# OneSLiPoCharger.net
KiCad netlist of a schematic drawn in EAGLE
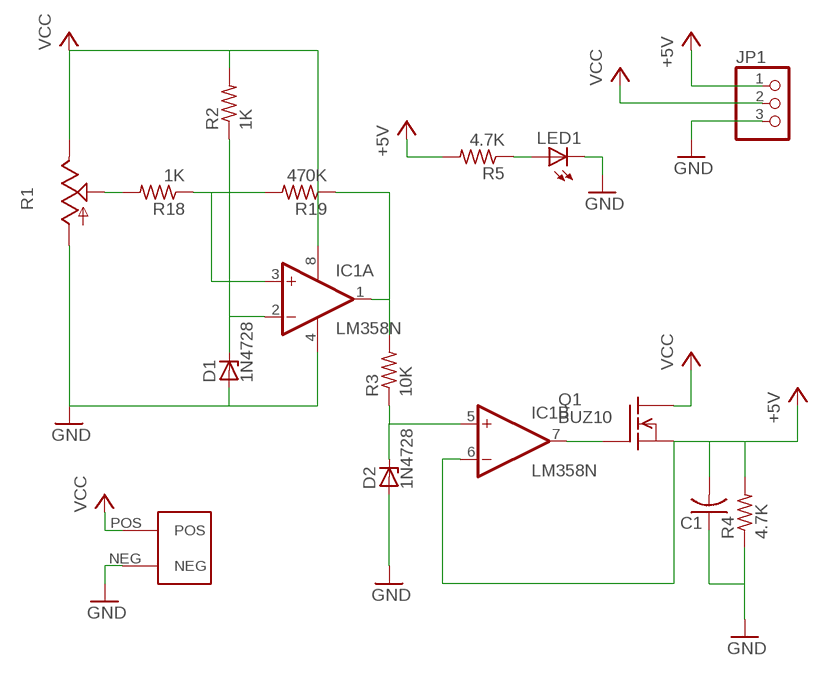
[diagram p0: schematic, sheet 1]
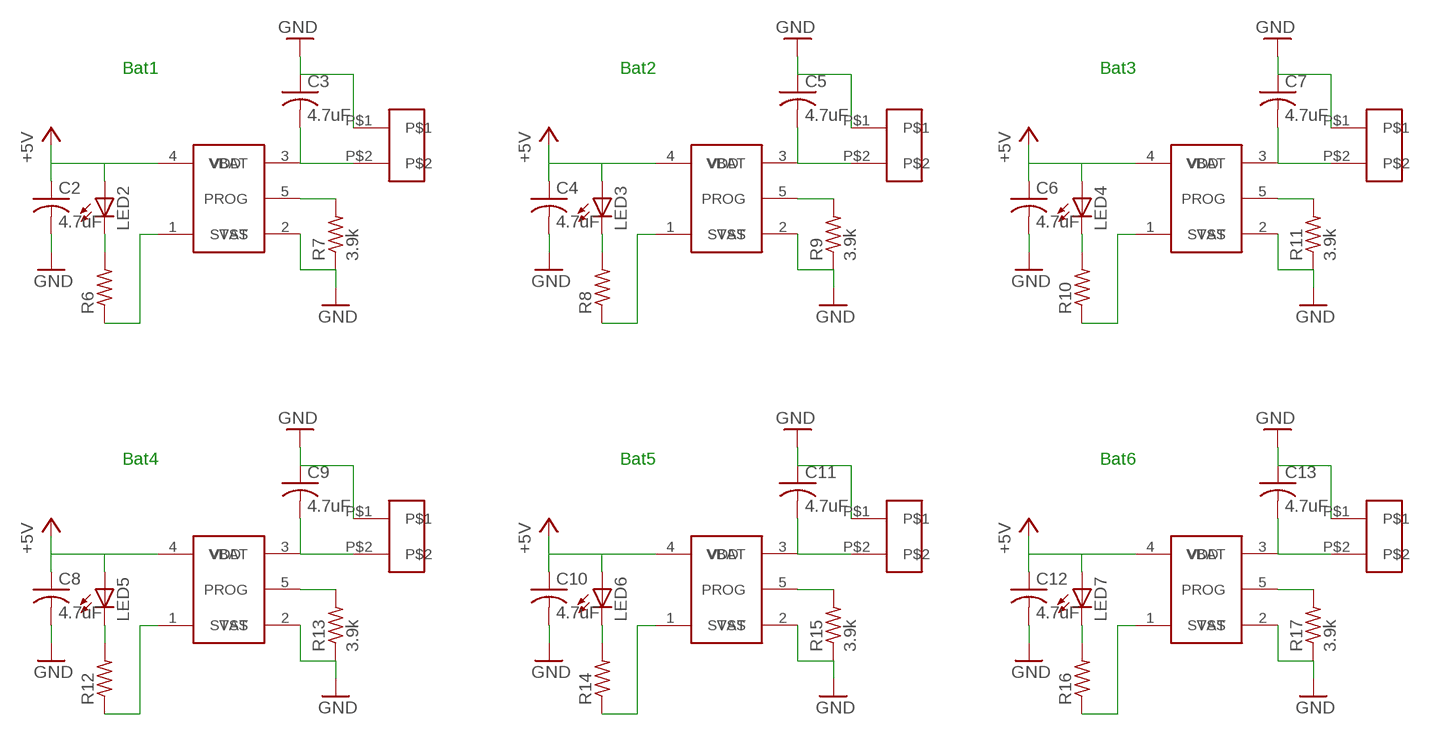
[diagram p1: schematic, sheet 2]

(export (version "E")
  (design (tool "Eeschema 10.0.6"))
  (components
    (comp (ref "C1")
      (value "C-US025-025X050")
      (footprint "eagle-import:C025-025X050")
      (libsource (lib "eagle-import") (part "C-US025-025X050"))
    )
    (comp (ref "D1")
      (value "1N4728")
      (footprint "eagle-import:DO41Z10")
      (libsource (lib "eagle-import") (part "1N4728"))
    )
    (comp (ref "D2")
      (value "1N4728")
      (footprint "eagle-import:DO41Z10")
      (libsource (lib "eagle-import") (part "1N4728"))
    )
    (comp (ref "IC1")
      (value "LM358N")
      (footprint "eagle-import:DIL08")
      (libsource (lib "eagle-import") (part "LM358N"))
    )
    (comp (ref "JP1")
      (value "PINHD-1X3")
      (footprint "eagle-import:1X03")
      (libsource (lib "eagle-import") (part "PINHD-1X3"))
    )
    (comp (ref "LED1")
      (value "LED3MM")
      (footprint "eagle-import:LED3MM")
      (libsource (lib "eagle-import") (part "LED3MM"))
    )
    (comp (ref "Q1")
      (value "BUZ10")
      (footprint "eagle-import:TO220")
      (libsource (lib "eagle-import") (part "BUZ10"))
    )
    (comp (ref "R1")
      (value "TRIM_US-B25P")
      (footprint "eagle-import:B25P")
      (libsource (lib "eagle-import") (part "TRIM_US-B25P"))
    )
    (comp (ref "R2")
      (value "1K")
      (footprint "eagle-import:0207_10")
      (libsource (lib "eagle-import") (part "R-US_0207/10"))
    )
    (comp (ref "R3")
      (value "10K")
      (footprint "eagle-import:0207_10")
      (libsource (lib "eagle-import") (part "R-US_0207/10"))
    )
    (comp (ref "R4")
      (value "4.7K")
      (footprint "eagle-import:0207_10")
      (libsource (lib "eagle-import") (part "R-US_0207/10"))
    )
    (comp (ref "R5")
      (value "4.7K")
      (footprint "eagle-import:0207_10")
      (libsource (lib "eagle-import") (part "R-US_0207/10"))
    )
    (comp (ref "R18")
      (value "1K")
      (footprint "eagle-import:0207_10")
      (libsource (lib "eagle-import") (part "R-US_0207/10"))
    )
    (comp (ref "R19")
      (value "470K")
      (footprint "eagle-import:0207_10")
      (libsource (lib "eagle-import") (part "R-US_0207/10"))
    )
    (comp (ref "U$3")
      (value "XT60")
      (footprint "eagle-import:XT60")
      (libsource (lib "eagle-import") (part "XT60"))
    )
    (comp (ref "C2")
      (value "4.7uF")
      (footprint "eagle-import:C0805")
      (libsource (lib "eagle-import") (part "C-USC0805"))
    )
    (comp (ref "C3")
      (value "4.7uF")
      (footprint "eagle-import:C0805")
      (libsource (lib "eagle-import") (part "C-USC0805"))
    )
    (comp (ref "C4")
      (value "4.7uF")
      (footprint "eagle-import:C0805")
      (libsource (lib "eagle-import") (part "C-USC0805"))
    )
    (comp (ref "C5")
      (value "4.7uF")
      (footprint "eagle-import:C0805")
      (libsource (lib "eagle-import") (part "C-USC0805"))
    )
    (comp (ref "C6")
      (value "4.7uF")
      (footprint "eagle-import:C0805")
      (libsource (lib "eagle-import") (part "C-USC0805"))
    )
    (comp (ref "C7")
      (value "4.7uF")
      (footprint "eagle-import:C0805")
      (libsource (lib "eagle-import") (part "C-USC0805"))
    )
    (comp (ref "C8")
      (value "4.7uF")
      (footprint "eagle-import:C0805")
      (libsource (lib "eagle-import") (part "C-USC0805"))
    )
    (comp (ref "C9")
      (value "4.7uF")
      (footprint "eagle-import:C0805")
      (libsource (lib "eagle-import") (part "C-USC0805"))
    )
    (comp (ref "C10")
      (value "4.7uF")
      (footprint "eagle-import:C0805")
      (libsource (lib "eagle-import") (part "C-USC0805"))
    )
    (comp (ref "C11")
      (value "4.7uF")
      (footprint "eagle-import:C0805")
      (libsource (lib "eagle-import") (part "C-USC0805"))
    )
    (comp (ref "C12")
      (value "4.7uF")
      (footprint "eagle-import:C0805")
      (libsource (lib "eagle-import") (part "C-USC0805"))
    )
    (comp (ref "C13")
      (value "4.7uF")
      (footprint "eagle-import:C0805")
      (libsource (lib "eagle-import") (part "C-USC0805"))
    )
    (comp (ref "LED2")
      (value "LED3MM")
      (footprint "eagle-import:LED3MM")
      (libsource (lib "eagle-import") (part "LED3MM"))
    )
    (comp (ref "LED3")
      (value "LED3MM")
      (footprint "eagle-import:LED3MM")
      (libsource (lib "eagle-import") (part "LED3MM"))
    )
    (comp (ref "LED4")
      (value "LED3MM")
      (footprint "eagle-import:LED3MM")
      (libsource (lib "eagle-import") (part "LED3MM"))
    )
    (comp (ref "LED5")
      (value "LED3MM")
      (footprint "eagle-import:LED3MM")
      (libsource (lib "eagle-import") (part "LED3MM"))
    )
    (comp (ref "LED6")
      (value "LED3MM")
      (footprint "eagle-import:LED3MM")
      (libsource (lib "eagle-import") (part "LED3MM"))
    )
    (comp (ref "LED7")
      (value "LED3MM")
      (footprint "eagle-import:LED3MM")
      (libsource (lib "eagle-import") (part "LED3MM"))
    )
    (comp (ref "R6")
      (value "R-US_M0805")
      (footprint "eagle-import:M0805")
      (libsource (lib "eagle-import") (part "R-US_M0805"))
    )
    (comp (ref "R7")
      (value "3.9k")
      (footprint "eagle-import:M0805")
      (libsource (lib "eagle-import") (part "R-US_M0805"))
    )
    (comp (ref "R8")
      (value "R-US_M0805")
      (footprint "eagle-import:M0805")
      (libsource (lib "eagle-import") (part "R-US_M0805"))
    )
    (comp (ref "R9")
      (value "3.9k")
      (footprint "eagle-import:M0805")
      (libsource (lib "eagle-import") (part "R-US_M0805"))
    )
    (comp (ref "R10")
      (value "R-US_M0805")
      (footprint "eagle-import:M0805")
      (libsource (lib "eagle-import") (part "R-US_M0805"))
    )
    (comp (ref "R11")
      (value "3.9k")
      (footprint "eagle-import:M0805")
      (libsource (lib "eagle-import") (part "R-US_M0805"))
    )
    (comp (ref "R12")
      (value "R-US_M0805")
      (footprint "eagle-import:M0805")
      (libsource (lib "eagle-import") (part "R-US_M0805"))
    )
    (comp (ref "R13")
      (value "3.9k")
      (footprint "eagle-import:M0805")
      (libsource (lib "eagle-import") (part "R-US_M0805"))
    )
    (comp (ref "R14")
      (value "R-US_M0805")
      (footprint "eagle-import:M0805")
      (libsource (lib "eagle-import") (part "R-US_M0805"))
    )
    (comp (ref "R15")
      (value "3.9k")
      (footprint "eagle-import:M0805")
      (libsource (lib "eagle-import") (part "R-US_M0805"))
    )
    (comp (ref "R16")
      (value "R-US_M0805")
      (footprint "eagle-import:M0805")
      (libsource (lib "eagle-import") (part "R-US_M0805"))
    )
    (comp (ref "R17")
      (value "3.9k")
      (footprint "eagle-import:M0805")
      (libsource (lib "eagle-import") (part "R-US_M0805"))
    )
    (comp (ref "U$1")
      (value "MCP73831")
      (footprint "eagle-import:MCP73831-SOT23")
      (libsource (lib "eagle-import") (part "MCP73831"))
    )
    (comp (ref "U$2")
      (value "PICOBLADE-2PIN")
      (footprint "eagle-import:PICOBLADE-2PIN")
      (libsource (lib "eagle-import") (part "PICOBLADE-2PIN"))
    )
    (comp (ref "U$4")
      (value "MCP73831")
      (footprint "eagle-import:MCP73831-SOT23")
      (libsource (lib "eagle-import") (part "MCP73831"))
    )
    (comp (ref "U$5")
      (value "PICOBLADE-2PIN")
      (footprint "eagle-import:PICOBLADE-2PIN")
      (libsource (lib "eagle-import") (part "PICOBLADE-2PIN"))
    )
    (comp (ref "U$6")
      (value "MCP73831")
      (footprint "eagle-import:MCP73831-SOT23")
      (libsource (lib "eagle-import") (part "MCP73831"))
    )
    (comp (ref "U$7")
      (value "PICOBLADE-2PIN")
      (footprint "eagle-import:PICOBLADE-2PIN")
      (libsource (lib "eagle-import") (part "PICOBLADE-2PIN"))
    )
    (comp (ref "U$8")
      (value "MCP73831")
      (footprint "eagle-import:MCP73831-SOT23")
      (libsource (lib "eagle-import") (part "MCP73831"))
    )
    (comp (ref "U$9")
      (value "PICOBLADE-2PIN")
      (footprint "eagle-import:PICOBLADE-2PIN")
      (libsource (lib "eagle-import") (part "PICOBLADE-2PIN"))
    )
    (comp (ref "U$10")
      (value "MCP73831")
      (footprint "eagle-import:MCP73831-SOT23")
      (libsource (lib "eagle-import") (part "MCP73831"))
    )
    (comp (ref "U$11")
      (value "PICOBLADE-2PIN")
      (footprint "eagle-import:PICOBLADE-2PIN")
      (libsource (lib "eagle-import") (part "PICOBLADE-2PIN"))
    )
    (comp (ref "U$12")
      (value "MCP73831")
      (footprint "eagle-import:MCP73831-SOT23")
      (libsource (lib "eagle-import") (part "MCP73831"))
    )
    (comp (ref "U$13")
      (value "PICOBLADE-2PIN")
      (footprint "eagle-import:PICOBLADE-2PIN")
      (libsource (lib "eagle-import") (part "PICOBLADE-2PIN"))
    )
  )
  (nets
    (net (code "1") (name "+5V") (class "Default")
      (node (ref "C1") (pin "2") (pinfunction "2_2") (pintype "passive"))
      (node (ref "C10") (pin "1") (pinfunction "1_1") (pintype "passive"))
      (node (ref "C12") (pin "1") (pinfunction "1_1") (pintype "passive"))
      (node (ref "C2") (pin "1") (pinfunction "1_1") (pintype "passive"))
      (node (ref "C4") (pin "1") (pinfunction "1_1") (pintype "passive"))
      (node (ref "C6") (pin "1") (pinfunction "1_1") (pintype "passive"))
      (node (ref "C8") (pin "1") (pinfunction "1_1") (pintype "passive"))
      (node (ref "IC1") (pin "6") (pinfunction "-IN_6") (pintype "input"))
      (node (ref "JP1") (pin "1") (pinfunction "1_1") (pintype "passive"))
      (node (ref "LED2") (pin "A") (pinfunction "A_A") (pintype "passive"))
      (node (ref "LED3") (pin "A") (pinfunction "A_A") (pintype "passive"))
      (node (ref "LED4") (pin "A") (pinfunction "A_A") (pintype "passive"))
      (node (ref "LED5") (pin "A") (pinfunction "A_A") (pintype "passive"))
      (node (ref "LED6") (pin "A") (pinfunction "A_A") (pintype "passive"))
      (node (ref "LED7") (pin "A") (pinfunction "A_A") (pintype "passive"))
      (node (ref "Q1") (pin "3") (pinfunction "S_3") (pintype "passive"))
      (node (ref "R4") (pin "2") (pinfunction "2_2") (pintype "passive"))
      (node (ref "R5") (pin "2") (pinfunction "2_2") (pintype "passive"))
      (node (ref "U$1") (pin "4") (pinfunction "VDD_4") (pintype "bidirectional"))
      (node (ref "U$10") (pin "4") (pinfunction "VDD_4") (pintype "bidirectional"))
      (node (ref "U$12") (pin "4") (pinfunction "VDD_4") (pintype "bidirectional"))
      (node (ref "U$4") (pin "4") (pinfunction "VDD_4") (pintype "bidirectional"))
      (node (ref "U$6") (pin "4") (pinfunction "VDD_4") (pintype "bidirectional"))
      (node (ref "U$8") (pin "4") (pinfunction "VDD_4") (pintype "bidirectional"))
    )
    (net (code "2") (name "GND") (class "Default")
      (node (ref "C1") (pin "1") (pinfunction "1_1") (pintype "passive"))
      (node (ref "C10") (pin "2") (pinfunction "2_2") (pintype "passive"))
      (node (ref "C11") (pin "1") (pinfunction "1_1") (pintype "passive"))
      (node (ref "C12") (pin "2") (pinfunction "2_2") (pintype "passive"))
      (node (ref "C13") (pin "1") (pinfunction "1_1") (pintype "passive"))
      (node (ref "C2") (pin "2") (pinfunction "2_2") (pintype "passive"))
      (node (ref "C3") (pin "1") (pinfunction "1_1") (pintype "passive"))
      (node (ref "C4") (pin "2") (pinfunction "2_2") (pintype "passive"))
      (node (ref "C5") (pin "1") (pinfunction "1_1") (pintype "passive"))
      (node (ref "C6") (pin "2") (pinfunction "2_2") (pintype "passive"))
      (node (ref "C7") (pin "1") (pinfunction "1_1") (pintype "passive"))
      (node (ref "C8") (pin "2") (pinfunction "2_2") (pintype "passive"))
      (node (ref "C9") (pin "1") (pinfunction "1_1") (pintype "passive"))
      (node (ref "D1") (pin "A") (pinfunction "A_A") (pintype "passive"))
      (node (ref "D2") (pin "A") (pinfunction "A_A") (pintype "passive"))
      (node (ref "IC1") (pin "4") (pinfunction "V-_4") (pintype "power_in"))
      (node (ref "JP1") (pin "3") (pinfunction "3_3") (pintype "passive"))
      (node (ref "LED1") (pin "K") (pinfunction "C_K") (pintype "passive"))
      (node (ref "R1") (pin "A") (pinfunction "A_A") (pintype "passive"))
      (node (ref "R11") (pin "1") (pinfunction "1_1") (pintype "passive"))
      (node (ref "R13") (pin "1") (pinfunction "1_1") (pintype "passive"))
      (node (ref "R15") (pin "1") (pinfunction "1_1") (pintype "passive"))
      (node (ref "R17") (pin "1") (pinfunction "1_1") (pintype "passive"))
      (node (ref "R4") (pin "1") (pinfunction "1_1") (pintype "passive"))
      (node (ref "R7") (pin "1") (pinfunction "1_1") (pintype "passive"))
      (node (ref "R9") (pin "1") (pinfunction "1_1") (pintype "passive"))
      (node (ref "U$1") (pin "2") (pinfunction "VSS_2") (pintype "bidirectional"))
      (node (ref "U$10") (pin "2") (pinfunction "VSS_2") (pintype "bidirectional"))
      (node (ref "U$11") (pin "P$1") (pinfunction "P$1_P$1") (pintype "bidirectional"))
      (node (ref "U$12") (pin "2") (pinfunction "VSS_2") (pintype "bidirectional"))
      (node (ref "U$13") (pin "P$1") (pinfunction "P$1_P$1") (pintype "bidirectional"))
      (node (ref "U$2") (pin "P$1") (pinfunction "P$1_P$1") (pintype "bidirectional"))
      (node (ref "U$3") (pin "NEG") (pinfunction "NEG_NEG") (pintype "bidirectional"))
      (node (ref "U$4") (pin "2") (pinfunction "VSS_2") (pintype "bidirectional"))
      (node (ref "U$5") (pin "P$1") (pinfunction "P$1_P$1") (pintype "bidirectional"))
      (node (ref "U$6") (pin "2") (pinfunction "VSS_2") (pintype "bidirectional"))
      (node (ref "U$7") (pin "P$1") (pinfunction "P$1_P$1") (pintype "bidirectional"))
      (node (ref "U$8") (pin "2") (pinfunction "VSS_2") (pintype "bidirectional"))
      (node (ref "U$9") (pin "P$1") (pinfunction "P$1_P$1") (pintype "bidirectional"))
    )
    (net (code "3") (name "Net-(IC1A-+IN)") (class "Default")
      (node (ref "IC1") (pin "3") (pinfunction "+IN_3") (pintype "input"))
      (node (ref "R18") (pin "1") (pinfunction "1_1") (pintype "passive"))
      (node (ref "R19") (pin "2") (pinfunction "2_2") (pintype "passive"))
    )
    (net (code "4") (name "Net-(IC1A--IN)") (class "Default")
      (node (ref "D1") (pin "C") (pinfunction "C_C") (pintype "passive"))
      (node (ref "IC1") (pin "2") (pinfunction "-IN_2") (pintype "input"))
      (node (ref "R2") (pin "1") (pinfunction "1_1") (pintype "passive"))
    )
    (net (code "5") (name "Net-(IC1A-OUT)") (class "Default")
      (node (ref "IC1") (pin "1") (pinfunction "OUT_1") (pintype "output"))
      (node (ref "R19") (pin "1") (pinfunction "1_1") (pintype "passive"))
      (node (ref "R3") (pin "2") (pinfunction "2_2") (pintype "passive"))
    )
    (net (code "6") (name "Net-(IC1B-+IN)") (class "Default")
      (node (ref "D2") (pin "C") (pinfunction "C_C") (pintype "passive"))
      (node (ref "IC1") (pin "5") (pinfunction "+IN_5") (pintype "input"))
      (node (ref "R3") (pin "1") (pinfunction "1_1") (pintype "passive"))
    )
    (net (code "7") (name "Net-(IC1B-OUT)") (class "Default")
      (node (ref "IC1") (pin "7") (pinfunction "OUT_7") (pintype "output"))
      (node (ref "Q1") (pin "1") (pinfunction "G_1") (pintype "passive"))
    )
    (net (code "8") (name "Net-(LED1-PadA)") (class "Default")
      (node (ref "LED1") (pin "A") (pinfunction "A_A") (pintype "passive"))
      (node (ref "R5") (pin "1") (pinfunction "1_1") (pintype "passive"))
    )
    (net (code "9") (name "Net-(LED2-C)") (class "Default")
      (node (ref "LED2") (pin "K") (pinfunction "C_K") (pintype "passive"))
      (node (ref "R6") (pin "2") (pinfunction "2_2") (pintype "passive"))
    )
    (net (code "10") (name "Net-(LED3-C)") (class "Default")
      (node (ref "LED3") (pin "K") (pinfunction "C_K") (pintype "passive"))
      (node (ref "R8") (pin "2") (pinfunction "2_2") (pintype "passive"))
    )
    (net (code "11") (name "Net-(LED4-C)") (class "Default")
      (node (ref "LED4") (pin "K") (pinfunction "C_K") (pintype "passive"))
      (node (ref "R10") (pin "2") (pinfunction "2_2") (pintype "passive"))
    )
    (net (code "12") (name "Net-(LED5-C)") (class "Default")
      (node (ref "LED5") (pin "K") (pinfunction "C_K") (pintype "passive"))
      (node (ref "R12") (pin "2") (pinfunction "2_2") (pintype "passive"))
    )
    (net (code "13") (name "Net-(LED6-C)") (class "Default")
      (node (ref "LED6") (pin "K") (pinfunction "C_K") (pintype "passive"))
      (node (ref "R14") (pin "2") (pinfunction "2_2") (pintype "passive"))
    )
    (net (code "14") (name "Net-(LED7-C)") (class "Default")
      (node (ref "LED7") (pin "K") (pinfunction "C_K") (pintype "passive"))
      (node (ref "R16") (pin "2") (pinfunction "2_2") (pintype "passive"))
    )
    (net (code "15") (name "Net-(R1-PadS)") (class "Default")
      (node (ref "R1") (pin "S") (pinfunction "S_S") (pintype "passive"))
      (node (ref "R18") (pin "2") (pinfunction "2_2") (pintype "passive"))
    )
    (net (code "16") (name "Net-(U$1-PROG)") (class "Default")
      (node (ref "R7") (pin "2") (pinfunction "2_2") (pintype "passive"))
      (node (ref "U$1") (pin "5") (pinfunction "PROG_5") (pintype "bidirectional"))
    )
    (net (code "17") (name "Net-(U$1-STAT)") (class "Default")
      (node (ref "R6") (pin "1") (pinfunction "1_1") (pintype "passive"))
      (node (ref "U$1") (pin "1") (pinfunction "STAT_1") (pintype "bidirectional"))
    )
    (net (code "18") (name "Net-(U$1-VBAT)") (class "Default")
      (node (ref "C3") (pin "2") (pinfunction "2_2") (pintype "passive"))
      (node (ref "U$1") (pin "3") (pinfunction "VBAT_3") (pintype "bidirectional"))
      (node (ref "U$2") (pin "P$2") (pinfunction "P$2_P$2") (pintype "bidirectional"))
    )
    (net (code "19") (name "Net-(U$4-PROG)") (class "Default")
      (node (ref "R9") (pin "2") (pinfunction "2_2") (pintype "passive"))
      (node (ref "U$4") (pin "5") (pinfunction "PROG_5") (pintype "bidirectional"))
    )
    (net (code "20") (name "Net-(U$4-STAT)") (class "Default")
      (node (ref "R8") (pin "1") (pinfunction "1_1") (pintype "passive"))
      (node (ref "U$4") (pin "1") (pinfunction "STAT_1") (pintype "bidirectional"))
    )
    (net (code "21") (name "Net-(U$4-VBAT)") (class "Default")
      (node (ref "C5") (pin "2") (pinfunction "2_2") (pintype "passive"))
      (node (ref "U$4") (pin "3") (pinfunction "VBAT_3") (pintype "bidirectional"))
      (node (ref "U$5") (pin "P$2") (pinfunction "P$2_P$2") (pintype "bidirectional"))
    )
    (net (code "22") (name "Net-(U$6-PROG)") (class "Default")
      (node (ref "R11") (pin "2") (pinfunction "2_2") (pintype "passive"))
      (node (ref "U$6") (pin "5") (pinfunction "PROG_5") (pintype "bidirectional"))
    )
    (net (code "23") (name "Net-(U$6-STAT)") (class "Default")
      (node (ref "R10") (pin "1") (pinfunction "1_1") (pintype "passive"))
      (node (ref "U$6") (pin "1") (pinfunction "STAT_1") (pintype "bidirectional"))
    )
    (net (code "24") (name "Net-(U$6-VBAT)") (class "Default")
      (node (ref "C7") (pin "2") (pinfunction "2_2") (pintype "passive"))
      (node (ref "U$6") (pin "3") (pinfunction "VBAT_3") (pintype "bidirectional"))
      (node (ref "U$7") (pin "P$2") (pinfunction "P$2_P$2") (pintype "bidirectional"))
    )
    (net (code "25") (name "Net-(U$8-PROG)") (class "Default")
      (node (ref "R13") (pin "2") (pinfunction "2_2") (pintype "passive"))
      (node (ref "U$8") (pin "5") (pinfunction "PROG_5") (pintype "bidirectional"))
    )
    (net (code "26") (name "Net-(U$8-STAT)") (class "Default")
      (node (ref "R12") (pin "1") (pinfunction "1_1") (pintype "passive"))
      (node (ref "U$8") (pin "1") (pinfunction "STAT_1") (pintype "bidirectional"))
    )
    (net (code "27") (name "Net-(U$8-VBAT)") (class "Default")
      (node (ref "C9") (pin "2") (pinfunction "2_2") (pintype "passive"))
      (node (ref "U$8") (pin "3") (pinfunction "VBAT_3") (pintype "bidirectional"))
      (node (ref "U$9") (pin "P$2") (pinfunction "P$2_P$2") (pintype "bidirectional"))
    )
    (net (code "28") (name "Net-(U$10-PROG)") (class "Default")
      (node (ref "R15") (pin "2") (pinfunction "2_2") (pintype "passive"))
      (node (ref "U$10") (pin "5") (pinfunction "PROG_5") (pintype "bidirectional"))
    )
    (net (code "29") (name "Net-(U$10-STAT)") (class "Default")
      (node (ref "R14") (pin "1") (pinfunction "1_1") (pintype "passive"))
      (node (ref "U$10") (pin "1") (pinfunction "STAT_1") (pintype "bidirectional"))
    )
    (net (code "30") (name "Net-(U$10-VBAT)") (class "Default")
      (node (ref "C11") (pin "2") (pinfunction "2_2") (pintype "passive"))
      (node (ref "U$10") (pin "3") (pinfunction "VBAT_3") (pintype "bidirectional"))
      (node (ref "U$11") (pin "P$2") (pinfunction "P$2_P$2") (pintype "bidirectional"))
    )
    (net (code "31") (name "Net-(U$12-PROG)") (class "Default")
      (node (ref "R17") (pin "2") (pinfunction "2_2") (pintype "passive"))
      (node (ref "U$12") (pin "5") (pinfunction "PROG_5") (pintype "bidirectional"))
    )
    (net (code "32") (name "Net-(U$12-STAT)") (class "Default")
      (node (ref "R16") (pin "1") (pinfunction "1_1") (pintype "passive"))
      (node (ref "U$12") (pin "1") (pinfunction "STAT_1") (pintype "bidirectional"))
    )
    (net (code "33") (name "Net-(U$12-VBAT)") (class "Default")
      (node (ref "C13") (pin "2") (pinfunction "2_2") (pintype "passive"))
      (node (ref "U$12") (pin "3") (pinfunction "VBAT_3") (pintype "bidirectional"))
      (node (ref "U$13") (pin "P$2") (pinfunction "P$2_P$2") (pintype "bidirectional"))
    )
    (net (code "34") (name "VCC") (class "Default")
      (node (ref "IC1") (pin "8") (pinfunction "V+_8") (pintype "power_in"))
      (node (ref "JP1") (pin "2") (pinfunction "2_2") (pintype "passive"))
      (node (ref "Q1") (pin "2") (pinfunction "D_2") (pintype "passive"))
      (node (ref "R1") (pin "E") (pinfunction "E_E") (pintype "passive"))
      (node (ref "R2") (pin "2") (pinfunction "2_2") (pintype "passive"))
      (node (ref "U$3") (pin "POS") (pinfunction "POS_POS") (pintype "bidirectional"))
    )
  )
)
